# input.net
KiCad netlist of a schematic drawn in EAGLE
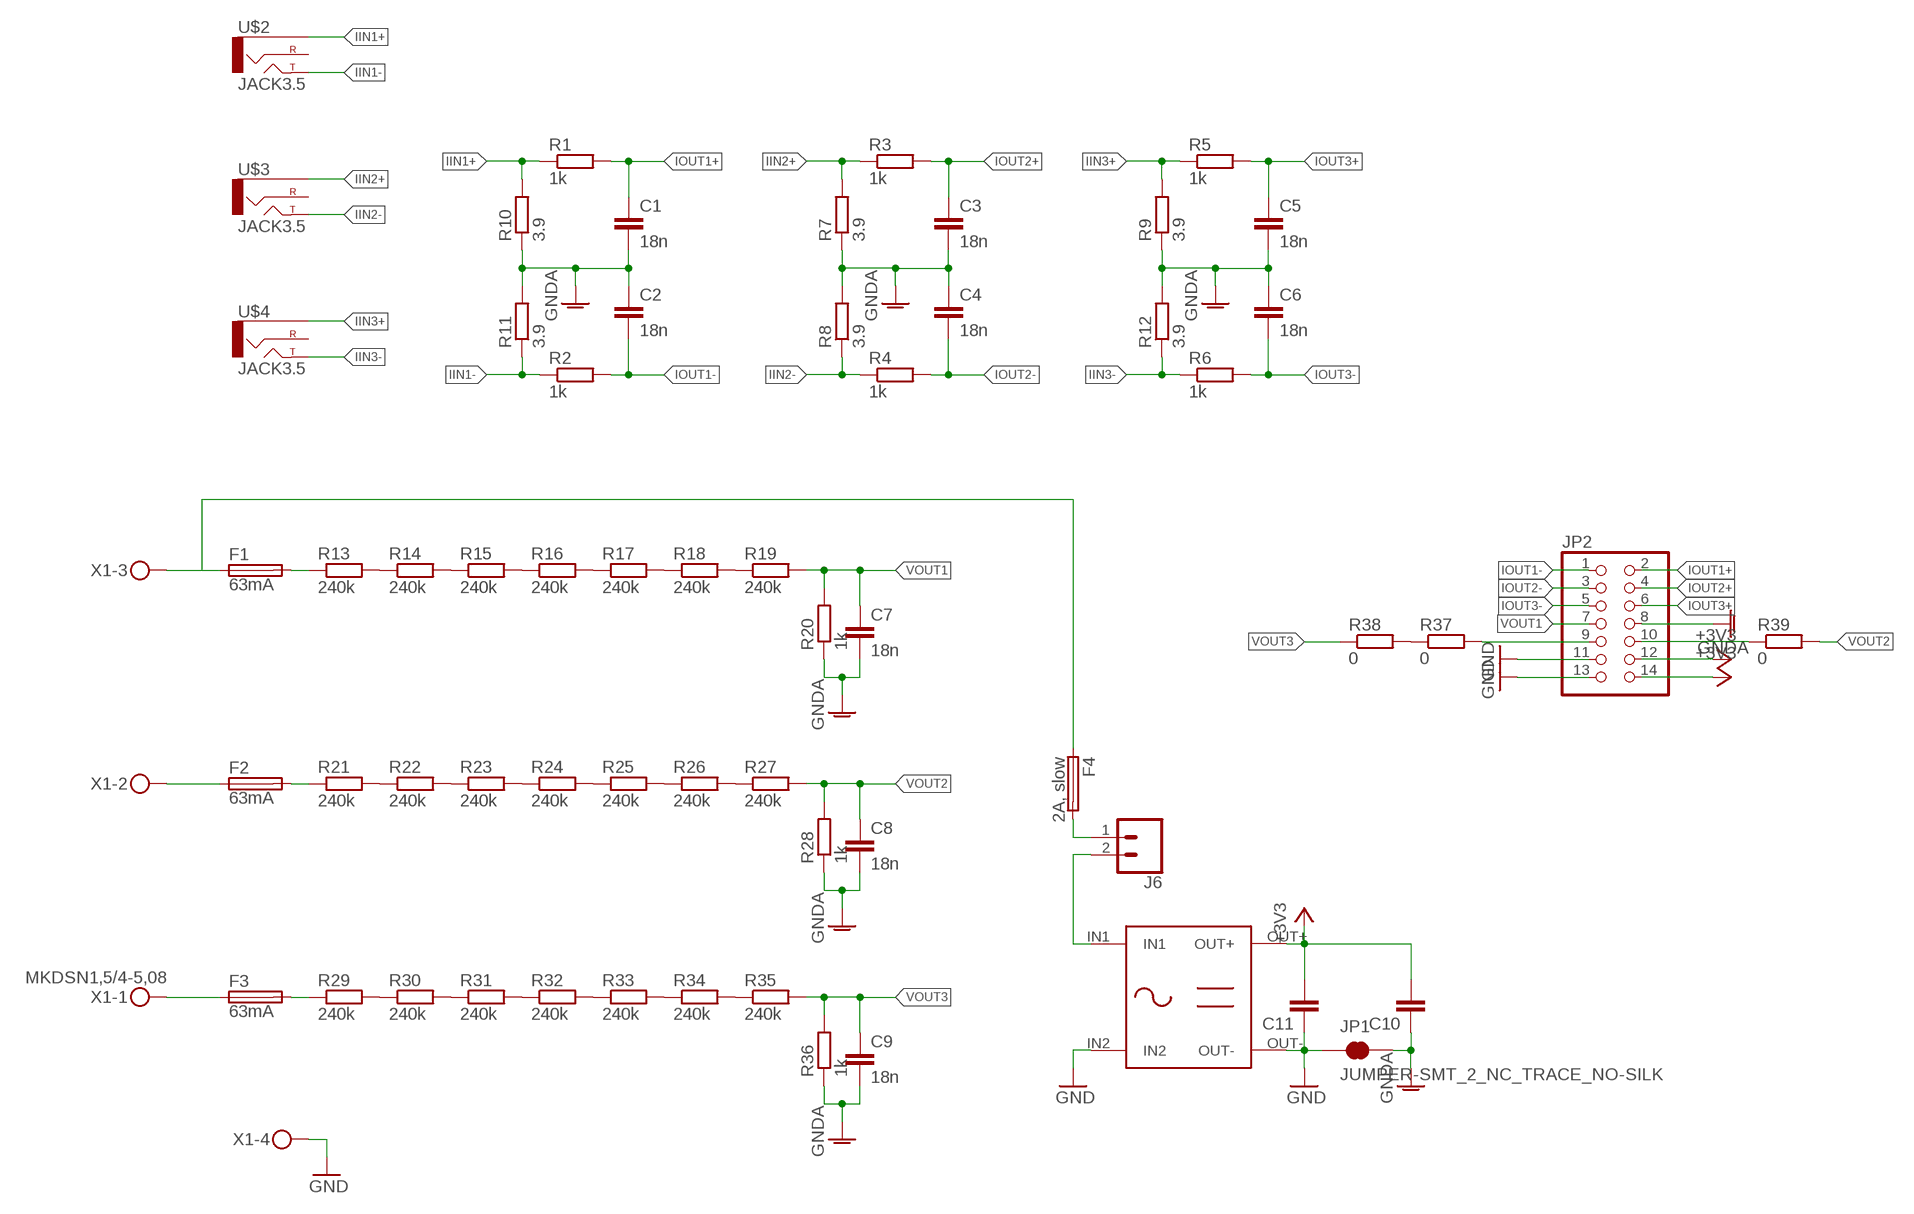
[diagram p0: schematic, sheet 1]

(export (version "E")
  (design (tool "Eeschema 10.0.6"))
  (components
    (comp (ref "C1")
      (value "18n")
      (footprint "eagle-import:C0805")
      (libsource (lib "eagle-import") (part "C-EUC0805"))
    )
    (comp (ref "C2")
      (value "18n")
      (footprint "eagle-import:C0805")
      (libsource (lib "eagle-import") (part "C-EUC0805"))
    )
    (comp (ref "C3")
      (value "18n")
      (footprint "eagle-import:C0805")
      (libsource (lib "eagle-import") (part "C-EUC0805"))
    )
    (comp (ref "C4")
      (value "18n")
      (footprint "eagle-import:C0805")
      (libsource (lib "eagle-import") (part "C-EUC0805"))
    )
    (comp (ref "C5")
      (value "18n")
      (footprint "eagle-import:C0805")
      (libsource (lib "eagle-import") (part "C-EUC0805"))
    )
    (comp (ref "C6")
      (value "18n")
      (footprint "eagle-import:C0805")
      (libsource (lib "eagle-import") (part "C-EUC0805"))
    )
    (comp (ref "C7")
      (value "18n")
      (footprint "eagle-import:C0805")
      (libsource (lib "eagle-import") (part "C-EUC0805"))
    )
    (comp (ref "C8")
      (value "18n")
      (footprint "eagle-import:C0805")
      (libsource (lib "eagle-import") (part "C-EUC0805"))
    )
    (comp (ref "C9")
      (value "18n")
      (footprint "eagle-import:C0805")
      (libsource (lib "eagle-import") (part "C-EUC0805"))
    )
    (comp (ref "C10")
      (value "C-EUC1206")
      (footprint "eagle-import:C1206")
      (libsource (lib "eagle-import") (part "C-EUC1206"))
    )
    (comp (ref "C11")
      (value "C-EUC1206")
      (footprint "eagle-import:C1206")
      (libsource (lib "eagle-import") (part "C-EUC1206"))
    )
    (comp (ref "F1")
      (value "63mA")
      (footprint "eagle-import:SH25")
      (fields (field (name "MF") "SCHURTER") (field (name "MPN") "0031.8211"))
      (libsource (lib "eagle-import") (part "SH25"))
    )
    (comp (ref "F2")
      (value "63mA")
      (footprint "eagle-import:SH25")
      (fields (field (name "MF") "SCHURTER") (field (name "MPN") "0031.8211"))
      (libsource (lib "eagle-import") (part "SH25"))
    )
    (comp (ref "F3")
      (value "63mA")
      (footprint "eagle-import:SH25")
      (fields (field (name "MF") "SCHURTER") (field (name "MPN") "0031.8211"))
      (libsource (lib "eagle-import") (part "SH25"))
    )
    (comp (ref "F4")
      (value "2A, slow")
      (footprint "eagle-import:SH25")
      (fields (field (name "MF") "SCHURTER") (field (name "MPN") "0031.8211"))
      (libsource (lib "eagle-import") (part "SH25"))
    )
    (comp (ref "J6")
      (value "CONN_025MM")
      (footprint "eagle-import:SCREWTERMINAL-5MM-2")
      (libsource (lib "eagle-import") (part "CONN_025MM"))
    )
    (comp (ref "JP1")
      (value "JUMPER-SMT_2_NC_TRACE_NO-SILK")
      (footprint "eagle-import:SMT-JUMPER_2_NC_TRACE_NO-SILK")
      (libsource (lib "eagle-import") (part "JUMPER-SMT_2_NC_TRACE_NO-SILK"))
    )
    (comp (ref "JP2")
      (value "PINHD-2X7")
      (footprint "eagle-import:2X07")
      (libsource (lib "eagle-import") (part "PINHD-2X7"))
    )
    (comp (ref "R1")
      (value "1k")
      (footprint "eagle-import:M0805")
      (libsource (lib "eagle-import") (part "R-EU_M0805"))
    )
    (comp (ref "R2")
      (value "1k")
      (footprint "eagle-import:M0805")
      (libsource (lib "eagle-import") (part "R-EU_M0805"))
    )
    (comp (ref "R3")
      (value "1k")
      (footprint "eagle-import:M0805")
      (libsource (lib "eagle-import") (part "R-EU_M0805"))
    )
    (comp (ref "R4")
      (value "1k")
      (footprint "eagle-import:M0805")
      (libsource (lib "eagle-import") (part "R-EU_M0805"))
    )
    (comp (ref "R5")
      (value "1k")
      (footprint "eagle-import:M0805")
      (libsource (lib "eagle-import") (part "R-EU_M0805"))
    )
    (comp (ref "R6")
      (value "1k")
      (footprint "eagle-import:M0805")
      (libsource (lib "eagle-import") (part "R-EU_M0805"))
    )
    (comp (ref "R7")
      (value "3.9")
      (footprint "eagle-import:M0805")
      (libsource (lib "eagle-import") (part "R-EU_M0805"))
    )
    (comp (ref "R8")
      (value "3.9")
      (footprint "eagle-import:M0805")
      (libsource (lib "eagle-import") (part "R-EU_M0805"))
    )
    (comp (ref "R9")
      (value "3.9")
      (footprint "eagle-import:M0805")
      (libsource (lib "eagle-import") (part "R-EU_M0805"))
    )
    (comp (ref "R10")
      (value "3.9")
      (footprint "eagle-import:M0805")
      (libsource (lib "eagle-import") (part "R-EU_M0805"))
    )
    (comp (ref "R11")
      (value "3.9")
      (footprint "eagle-import:M0805")
      (libsource (lib "eagle-import") (part "R-EU_M0805"))
    )
    (comp (ref "R12")
      (value "3.9")
      (footprint "eagle-import:M0805")
      (libsource (lib "eagle-import") (part "R-EU_M0805"))
    )
    (comp (ref "R13")
      (value "240k")
      (footprint "eagle-import:R1206")
      (libsource (lib "eagle-import") (part "R-EU_R1206"))
    )
    (comp (ref "R14")
      (value "240k")
      (footprint "eagle-import:R1206")
      (libsource (lib "eagle-import") (part "R-EU_R1206"))
    )
    (comp (ref "R15")
      (value "240k")
      (footprint "eagle-import:R1206")
      (libsource (lib "eagle-import") (part "R-EU_R1206"))
    )
    (comp (ref "R16")
      (value "240k")
      (footprint "eagle-import:R1206")
      (libsource (lib "eagle-import") (part "R-EU_R1206"))
    )
    (comp (ref "R17")
      (value "240k")
      (footprint "eagle-import:R1206")
      (libsource (lib "eagle-import") (part "R-EU_R1206"))
    )
    (comp (ref "R18")
      (value "240k")
      (footprint "eagle-import:R1206")
      (libsource (lib "eagle-import") (part "R-EU_R1206"))
    )
    (comp (ref "R19")
      (value "240k")
      (footprint "eagle-import:R1206")
      (libsource (lib "eagle-import") (part "R-EU_R1206"))
    )
    (comp (ref "R20")
      (value "1k")
      (footprint "eagle-import:M0805")
      (libsource (lib "eagle-import") (part "R-EU_M0805"))
    )
    (comp (ref "R21")
      (value "240k")
      (footprint "eagle-import:R1206")
      (libsource (lib "eagle-import") (part "R-EU_R1206"))
    )
    (comp (ref "R22")
      (value "240k")
      (footprint "eagle-import:R1206")
      (libsource (lib "eagle-import") (part "R-EU_R1206"))
    )
    (comp (ref "R23")
      (value "240k")
      (footprint "eagle-import:R1206")
      (libsource (lib "eagle-import") (part "R-EU_R1206"))
    )
    (comp (ref "R24")
      (value "240k")
      (footprint "eagle-import:R1206")
      (libsource (lib "eagle-import") (part "R-EU_R1206"))
    )
    (comp (ref "R25")
      (value "240k")
      (footprint "eagle-import:R1206")
      (libsource (lib "eagle-import") (part "R-EU_R1206"))
    )
    (comp (ref "R26")
      (value "240k")
      (footprint "eagle-import:R1206")
      (libsource (lib "eagle-import") (part "R-EU_R1206"))
    )
    (comp (ref "R27")
      (value "240k")
      (footprint "eagle-import:R1206")
      (libsource (lib "eagle-import") (part "R-EU_R1206"))
    )
    (comp (ref "R28")
      (value "1k")
      (footprint "eagle-import:M0805")
      (libsource (lib "eagle-import") (part "R-EU_M0805"))
    )
    (comp (ref "R29")
      (value "240k")
      (footprint "eagle-import:R1206")
      (libsource (lib "eagle-import") (part "R-EU_R1206"))
    )
    (comp (ref "R30")
      (value "240k")
      (footprint "eagle-import:R1206")
      (libsource (lib "eagle-import") (part "R-EU_R1206"))
    )
    (comp (ref "R31")
      (value "240k")
      (footprint "eagle-import:R1206")
      (libsource (lib "eagle-import") (part "R-EU_R1206"))
    )
    (comp (ref "R32")
      (value "240k")
      (footprint "eagle-import:R1206")
      (libsource (lib "eagle-import") (part "R-EU_R1206"))
    )
    (comp (ref "R33")
      (value "240k")
      (footprint "eagle-import:R1206")
      (libsource (lib "eagle-import") (part "R-EU_R1206"))
    )
    (comp (ref "R34")
      (value "240k")
      (footprint "eagle-import:R1206")
      (libsource (lib "eagle-import") (part "R-EU_R1206"))
    )
    (comp (ref "R35")
      (value "240k")
      (footprint "eagle-import:R1206")
      (libsource (lib "eagle-import") (part "R-EU_R1206"))
    )
    (comp (ref "R36")
      (value "1k")
      (footprint "eagle-import:M0805")
      (libsource (lib "eagle-import") (part "R-EU_M0805"))
    )
    (comp (ref "R37")
      (value "0")
      (footprint "eagle-import:R1206")
      (libsource (lib "eagle-import") (part "R-EU_R1206"))
    )
    (comp (ref "R38")
      (value "0")
      (footprint "eagle-import:R1206")
      (libsource (lib "eagle-import") (part "R-EU_R1206"))
    )
    (comp (ref "R39")
      (value "0")
      (footprint "eagle-import:R1206")
      (libsource (lib "eagle-import") (part "R-EU_R1206"))
    )
    (comp (ref "U$1")
      (value "MW-IRM")
      (footprint "eagle-import:MW-IRM-DIP")
      (libsource (lib "eagle-import") (part "MW-IRM"))
    )
    (comp (ref "U$2")
      (value "JACK3.5")
      (footprint "eagle-import:AUDIO-JACK")
      (libsource (lib "eagle-import") (part "JACK3.5"))
    )
    (comp (ref "U$3")
      (value "JACK3.5")
      (footprint "eagle-import:AUDIO-JACK")
      (libsource (lib "eagle-import") (part "JACK3.5"))
    )
    (comp (ref "U$4")
      (value "JACK3.5")
      (footprint "eagle-import:AUDIO-JACK")
      (libsource (lib "eagle-import") (part "JACK3.5"))
    )
    (comp (ref "X1")
      (value "MKDSN1,5/4-5,08")
      (footprint "eagle-import:MKDSN1,5_4-5,08")
      (libsource (lib "eagle-import") (part "MKDSN1,5/4-5,08"))
    )
  )
  (nets
    (net (code "1") (name "+3V3") (class "Default")
      (node (ref "C10") (pin "2") (pinfunction "2_2") (pintype "passive"))
      (node (ref "C11") (pin "2") (pinfunction "2_2") (pintype "passive"))
      (node (ref "JP2") (pin "12") (pinfunction "12_12") (pintype "passive"))
      (node (ref "JP2") (pin "14") (pinfunction "14_14") (pintype "passive"))
      (node (ref "U$1") (pin "OUT+") (pinfunction "OUT+_OUT+") (pintype "bidirectional"))
    )
    (net (code "2") (name "GND") (class "Default")
      (node (ref "C11") (pin "1") (pinfunction "1_1") (pintype "passive"))
      (node (ref "JP1") (pin "1") (pinfunction "1_1") (pintype "passive"))
      (node (ref "JP2") (pin "11") (pinfunction "11_11") (pintype "passive"))
      (node (ref "JP2") (pin "13") (pinfunction "13_13") (pintype "passive"))
      (node (ref "U$1") (pin "IN2") (pinfunction "IN2_IN2") (pintype "bidirectional"))
      (node (ref "U$1") (pin "OUT-") (pinfunction "OUT-_OUT-") (pintype "bidirectional"))
      (node (ref "X1") (pin "4") (pinfunction "KL_4") (pintype "passive"))
    )
    (net (code "3") (name "GNDA") (class "Default")
      (node (ref "C1") (pin "2") (pinfunction "2_2") (pintype "passive"))
      (node (ref "C10") (pin "1") (pinfunction "1_1") (pintype "passive"))
      (node (ref "C2") (pin "1") (pinfunction "1_1") (pintype "passive"))
      (node (ref "C3") (pin "2") (pinfunction "2_2") (pintype "passive"))
      (node (ref "C4") (pin "1") (pinfunction "1_1") (pintype "passive"))
      (node (ref "C5") (pin "2") (pinfunction "2_2") (pintype "passive"))
      (node (ref "C6") (pin "1") (pinfunction "1_1") (pintype "passive"))
      (node (ref "C7") (pin "2") (pinfunction "2_2") (pintype "passive"))
      (node (ref "C8") (pin "2") (pinfunction "2_2") (pintype "passive"))
      (node (ref "C9") (pin "2") (pinfunction "2_2") (pintype "passive"))
      (node (ref "JP1") (pin "2") (pinfunction "2_2") (pintype "passive"))
      (node (ref "JP2") (pin "8") (pinfunction "8_8") (pintype "passive"))
      (node (ref "R10") (pin "1") (pinfunction "1_1") (pintype "passive"))
      (node (ref "R11") (pin "2") (pinfunction "2_2") (pintype "passive"))
      (node (ref "R12") (pin "2") (pinfunction "2_2") (pintype "passive"))
      (node (ref "R20") (pin "1") (pinfunction "1_1") (pintype "passive"))
      (node (ref "R28") (pin "1") (pinfunction "1_1") (pintype "passive"))
      (node (ref "R36") (pin "1") (pinfunction "1_1") (pintype "passive"))
      (node (ref "R7") (pin "1") (pinfunction "1_1") (pintype "passive"))
      (node (ref "R8") (pin "2") (pinfunction "2_2") (pintype "passive"))
      (node (ref "R9") (pin "1") (pinfunction "1_1") (pintype "passive"))
    )
    (net (code "4") (name "IIN1+") (class "Default")
      (node (ref "R1") (pin "1") (pinfunction "1_1") (pintype "passive"))
      (node (ref "R10") (pin "2") (pinfunction "2_2") (pintype "passive"))
      (node (ref "U$2") (pin "SLEEVE") (pinfunction "SLEEVE_SLEEVE") (pintype "bidirectional"))
    )
    (net (code "5") (name "IIN1-") (class "Default")
      (node (ref "R11") (pin "1") (pinfunction "1_1") (pintype "passive"))
      (node (ref "R2") (pin "1") (pinfunction "1_1") (pintype "passive"))
      (node (ref "U$2") (pin "TIP") (pinfunction "TIP_TIP") (pintype "bidirectional"))
    )
    (net (code "6") (name "IIN2+") (class "Default")
      (node (ref "R3") (pin "1") (pinfunction "1_1") (pintype "passive"))
      (node (ref "R7") (pin "2") (pinfunction "2_2") (pintype "passive"))
      (node (ref "U$3") (pin "SLEEVE") (pinfunction "SLEEVE_SLEEVE") (pintype "bidirectional"))
    )
    (net (code "7") (name "IIN2-") (class "Default")
      (node (ref "R4") (pin "1") (pinfunction "1_1") (pintype "passive"))
      (node (ref "R8") (pin "1") (pinfunction "1_1") (pintype "passive"))
      (node (ref "U$3") (pin "TIP") (pinfunction "TIP_TIP") (pintype "bidirectional"))
    )
    (net (code "8") (name "IIN3+") (class "Default")
      (node (ref "R5") (pin "1") (pinfunction "1_1") (pintype "passive"))
      (node (ref "R9") (pin "2") (pinfunction "2_2") (pintype "passive"))
      (node (ref "U$4") (pin "SLEEVE") (pinfunction "SLEEVE_SLEEVE") (pintype "bidirectional"))
    )
    (net (code "9") (name "IIN3-") (class "Default")
      (node (ref "R12") (pin "1") (pinfunction "1_1") (pintype "passive"))
      (node (ref "R6") (pin "1") (pinfunction "1_1") (pintype "passive"))
      (node (ref "U$4") (pin "TIP") (pinfunction "TIP_TIP") (pintype "bidirectional"))
    )
    (net (code "10") (name "IOUT1+") (class "Default")
      (node (ref "C1") (pin "1") (pinfunction "1_1") (pintype "passive"))
      (node (ref "JP2") (pin "2") (pinfunction "2_2") (pintype "passive"))
      (node (ref "R1") (pin "2") (pinfunction "2_2") (pintype "passive"))
    )
    (net (code "11") (name "IOUT1-") (class "Default")
      (node (ref "C2") (pin "2") (pinfunction "2_2") (pintype "passive"))
      (node (ref "JP2") (pin "1") (pinfunction "1_1") (pintype "passive"))
      (node (ref "R2") (pin "2") (pinfunction "2_2") (pintype "passive"))
    )
    (net (code "12") (name "IOUT2+") (class "Default")
      (node (ref "C3") (pin "1") (pinfunction "1_1") (pintype "passive"))
      (node (ref "JP2") (pin "4") (pinfunction "4_4") (pintype "passive"))
      (node (ref "R3") (pin "2") (pinfunction "2_2") (pintype "passive"))
    )
    (net (code "13") (name "IOUT2-") (class "Default")
      (node (ref "C4") (pin "2") (pinfunction "2_2") (pintype "passive"))
      (node (ref "JP2") (pin "3") (pinfunction "3_3") (pintype "passive"))
      (node (ref "R4") (pin "2") (pinfunction "2_2") (pintype "passive"))
    )
    (net (code "14") (name "IOUT3+") (class "Default")
      (node (ref "C5") (pin "1") (pinfunction "1_1") (pintype "passive"))
      (node (ref "JP2") (pin "6") (pinfunction "6_6") (pintype "passive"))
      (node (ref "R5") (pin "2") (pinfunction "2_2") (pintype "passive"))
    )
    (net (code "15") (name "IOUT3-") (class "Default")
      (node (ref "C6") (pin "2") (pinfunction "2_2") (pintype "passive"))
      (node (ref "JP2") (pin "5") (pinfunction "5_5") (pintype "passive"))
      (node (ref "R6") (pin "2") (pinfunction "2_2") (pintype "passive"))
    )
    (net (code "16") (name "Net-(F1-Pad2)") (class "Default")
      (node (ref "F1") (pin "2") (pinfunction "2_2") (pintype "passive"))
      (node (ref "R13") (pin "1") (pinfunction "1_1") (pintype "passive"))
    )
    (net (code "17") (name "Net-(F2-Pad2)") (class "Default")
      (node (ref "F2") (pin "2") (pinfunction "2_2") (pintype "passive"))
      (node (ref "R21") (pin "1") (pinfunction "1_1") (pintype "passive"))
    )
    (net (code "18") (name "Net-(F3-Pad2)") (class "Default")
      (node (ref "F3") (pin "2") (pinfunction "2_2") (pintype "passive"))
      (node (ref "R29") (pin "1") (pinfunction "1_1") (pintype "passive"))
    )
    (net (code "19") (name "Net-(F4-Pad2)") (class "Default")
      (node (ref "F4") (pin "2") (pinfunction "2_2") (pintype "passive"))
      (node (ref "J6") (pin "1") (pinfunction "1_1") (pintype "passive"))
    )
    (net (code "20") (name "Net-(J6-Pad2)") (class "Default")
      (node (ref "J6") (pin "2") (pinfunction "2_2") (pintype "passive"))
      (node (ref "U$1") (pin "IN1") (pinfunction "IN1_IN1") (pintype "bidirectional"))
    )
    (net (code "21") (name "Net-(JP2-Pad9)") (class "Default")
      (node (ref "JP2") (pin "9") (pinfunction "9_9") (pintype "passive"))
      (node (ref "R37") (pin "2") (pinfunction "2_2") (pintype "passive"))
    )
    (net (code "22") (name "Net-(JP2-Pad10)") (class "Default")
      (node (ref "JP2") (pin "10") (pinfunction "10_10") (pintype "passive"))
      (node (ref "R39") (pin "1") (pinfunction "1_1") (pintype "passive"))
    )
    (net (code "23") (name "Net-(R13-Pad2)") (class "Default")
      (node (ref "R13") (pin "2") (pinfunction "2_2") (pintype "passive"))
      (node (ref "R14") (pin "1") (pinfunction "1_1") (pintype "passive"))
    )
    (net (code "24") (name "Net-(R14-Pad2)") (class "Default")
      (node (ref "R14") (pin "2") (pinfunction "2_2") (pintype "passive"))
      (node (ref "R15") (pin "1") (pinfunction "1_1") (pintype "passive"))
    )
    (net (code "25") (name "Net-(R15-Pad2)") (class "Default")
      (node (ref "R15") (pin "2") (pinfunction "2_2") (pintype "passive"))
      (node (ref "R16") (pin "1") (pinfunction "1_1") (pintype "passive"))
    )
    (net (code "26") (name "Net-(R16-Pad2)") (class "Default")
      (node (ref "R16") (pin "2") (pinfunction "2_2") (pintype "passive"))
      (node (ref "R17") (pin "1") (pinfunction "1_1") (pintype "passive"))
    )
    (net (code "27") (name "Net-(R17-Pad2)") (class "Default")
      (node (ref "R17") (pin "2") (pinfunction "2_2") (pintype "passive"))
      (node (ref "R18") (pin "1") (pinfunction "1_1") (pintype "passive"))
    )
    (net (code "28") (name "Net-(R18-Pad2)") (class "Default")
      (node (ref "R18") (pin "2") (pinfunction "2_2") (pintype "passive"))
      (node (ref "R19") (pin "1") (pinfunction "1_1") (pintype "passive"))
    )
    (net (code "29") (name "Net-(R21-Pad2)") (class "Default")
      (node (ref "R21") (pin "2") (pinfunction "2_2") (pintype "passive"))
      (node (ref "R22") (pin "1") (pinfunction "1_1") (pintype "passive"))
    )
    (net (code "30") (name "Net-(R22-Pad2)") (class "Default")
      (node (ref "R22") (pin "2") (pinfunction "2_2") (pintype "passive"))
      (node (ref "R23") (pin "1") (pinfunction "1_1") (pintype "passive"))
    )
    (net (code "31") (name "Net-(R23-Pad2)") (class "Default")
      (node (ref "R23") (pin "2") (pinfunction "2_2") (pintype "passive"))
      (node (ref "R24") (pin "1") (pinfunction "1_1") (pintype "passive"))
    )
    (net (code "32") (name "Net-(R24-Pad2)") (class "Default")
      (node (ref "R24") (pin "2") (pinfunction "2_2") (pintype "passive"))
      (node (ref "R25") (pin "1") (pinfunction "1_1") (pintype "passive"))
    )
    (net (code "33") (name "Net-(R25-Pad2)") (class "Default")
      (node (ref "R25") (pin "2") (pinfunction "2_2") (pintype "passive"))
      (node (ref "R26") (pin "1") (pinfunction "1_1") (pintype "passive"))
    )
    (net (code "34") (name "Net-(R26-Pad2)") (class "Default")
      (node (ref "R26") (pin "2") (pinfunction "2_2") (pintype "passive"))
      (node (ref "R27") (pin "1") (pinfunction "1_1") (pintype "passive"))
    )
    (net (code "35") (name "Net-(R29-Pad2)") (class "Default")
      (node (ref "R29") (pin "2") (pinfunction "2_2") (pintype "passive"))
      (node (ref "R30") (pin "1") (pinfunction "1_1") (pintype "passive"))
    )
    (net (code "36") (name "Net-(R30-Pad2)") (class "Default")
      (node (ref "R30") (pin "2") (pinfunction "2_2") (pintype "passive"))
      (node (ref "R31") (pin "1") (pinfunction "1_1") (pintype "passive"))
    )
    (net (code "37") (name "Net-(R31-Pad2)") (class "Default")
      (node (ref "R31") (pin "2") (pinfunction "2_2") (pintype "passive"))
      (node (ref "R32") (pin "1") (pinfunction "1_1") (pintype "passive"))
    )
    (net (code "38") (name "Net-(R32-Pad2)") (class "Default")
      (node (ref "R32") (pin "2") (pinfunction "2_2") (pintype "passive"))
      (node (ref "R33") (pin "1") (pinfunction "1_1") (pintype "passive"))
    )
    (net (code "39") (name "Net-(R33-Pad2)") (class "Default")
      (node (ref "R33") (pin "2") (pinfunction "2_2") (pintype "passive"))
      (node (ref "R34") (pin "1") (pinfunction "1_1") (pintype "passive"))
    )
    (net (code "40") (name "Net-(R34-Pad2)") (class "Default")
      (node (ref "R34") (pin "2") (pinfunction "2_2") (pintype "passive"))
      (node (ref "R35") (pin "1") (pinfunction "1_1") (pintype "passive"))
    )
    (net (code "41") (name "Net-(R37-Pad1)") (class "Default")
      (node (ref "R37") (pin "1") (pinfunction "1_1") (pintype "passive"))
      (node (ref "R38") (pin "2") (pinfunction "2_2") (pintype "passive"))
    )
    (net (code "42") (name "Net-(X1A-KL)") (class "Default")
      (node (ref "F3") (pin "1") (pinfunction "1_1") (pintype "passive"))
      (node (ref "X1") (pin "1") (pinfunction "KL_1") (pintype "passive"))
    )
    (net (code "43") (name "Net-(X1B-KL)") (class "Default")
      (node (ref "F2") (pin "1") (pinfunction "1_1") (pintype "passive"))
      (node (ref "X1") (pin "2") (pinfunction "KL_2") (pintype "passive"))
    )
    (net (code "44") (name "Net-(X1C-KL)") (class "Default")
      (node (ref "F1") (pin "1") (pinfunction "1_1") (pintype "passive"))
      (node (ref "F4") (pin "1") (pinfunction "1_1") (pintype "passive"))
      (node (ref "X1") (pin "3") (pinfunction "KL_3") (pintype "passive"))
    )
    (net (code "45") (name "VOUT1") (class "Default")
      (node (ref "C7") (pin "1") (pinfunction "1_1") (pintype "passive"))
      (node (ref "JP2") (pin "7") (pinfunction "7_7") (pintype "passive"))
      (node (ref "R19") (pin "2") (pinfunction "2_2") (pintype "passive"))
      (node (ref "R20") (pin "2") (pinfunction "2_2") (pintype "passive"))
    )
    (net (code "46") (name "VOUT2") (class "Default")
      (node (ref "C8") (pin "1") (pinfunction "1_1") (pintype "passive"))
      (node (ref "R27") (pin "2") (pinfunction "2_2") (pintype "passive"))
      (node (ref "R28") (pin "2") (pinfunction "2_2") (pintype "passive"))
      (node (ref "R39") (pin "2") (pinfunction "2_2") (pintype "passive"))
    )
    (net (code "47") (name "VOUT3") (class "Default")
      (node (ref "C9") (pin "1") (pinfunction "1_1") (pintype "passive"))
      (node (ref "R35") (pin "2") (pinfunction "2_2") (pintype "passive"))
      (node (ref "R36") (pin "2") (pinfunction "2_2") (pintype "passive"))
      (node (ref "R38") (pin "1") (pinfunction "1_1") (pintype "passive"))
    )
    (net (code "48") (name "unconnected-(U$2-PadRING)") (class "Default")
      (node (ref "U$2") (pin "RING") (pinfunction "RING_RING") (pintype "bidirectional"))
    )
    (net (code "49") (name "unconnected-(U$3-PadRING)") (class "Default")
      (node (ref "U$3") (pin "RING") (pinfunction "RING_RING") (pintype "bidirectional"))
    )
    (net (code "50") (name "unconnected-(U$4-PadRING)") (class "Default")
      (node (ref "U$4") (pin "RING") (pinfunction "RING_RING") (pintype "bidirectional"))
    )
  )
)
